# brick_3pin_led_1x1.net
KiCad netlist of a schematic drawn in EAGLE
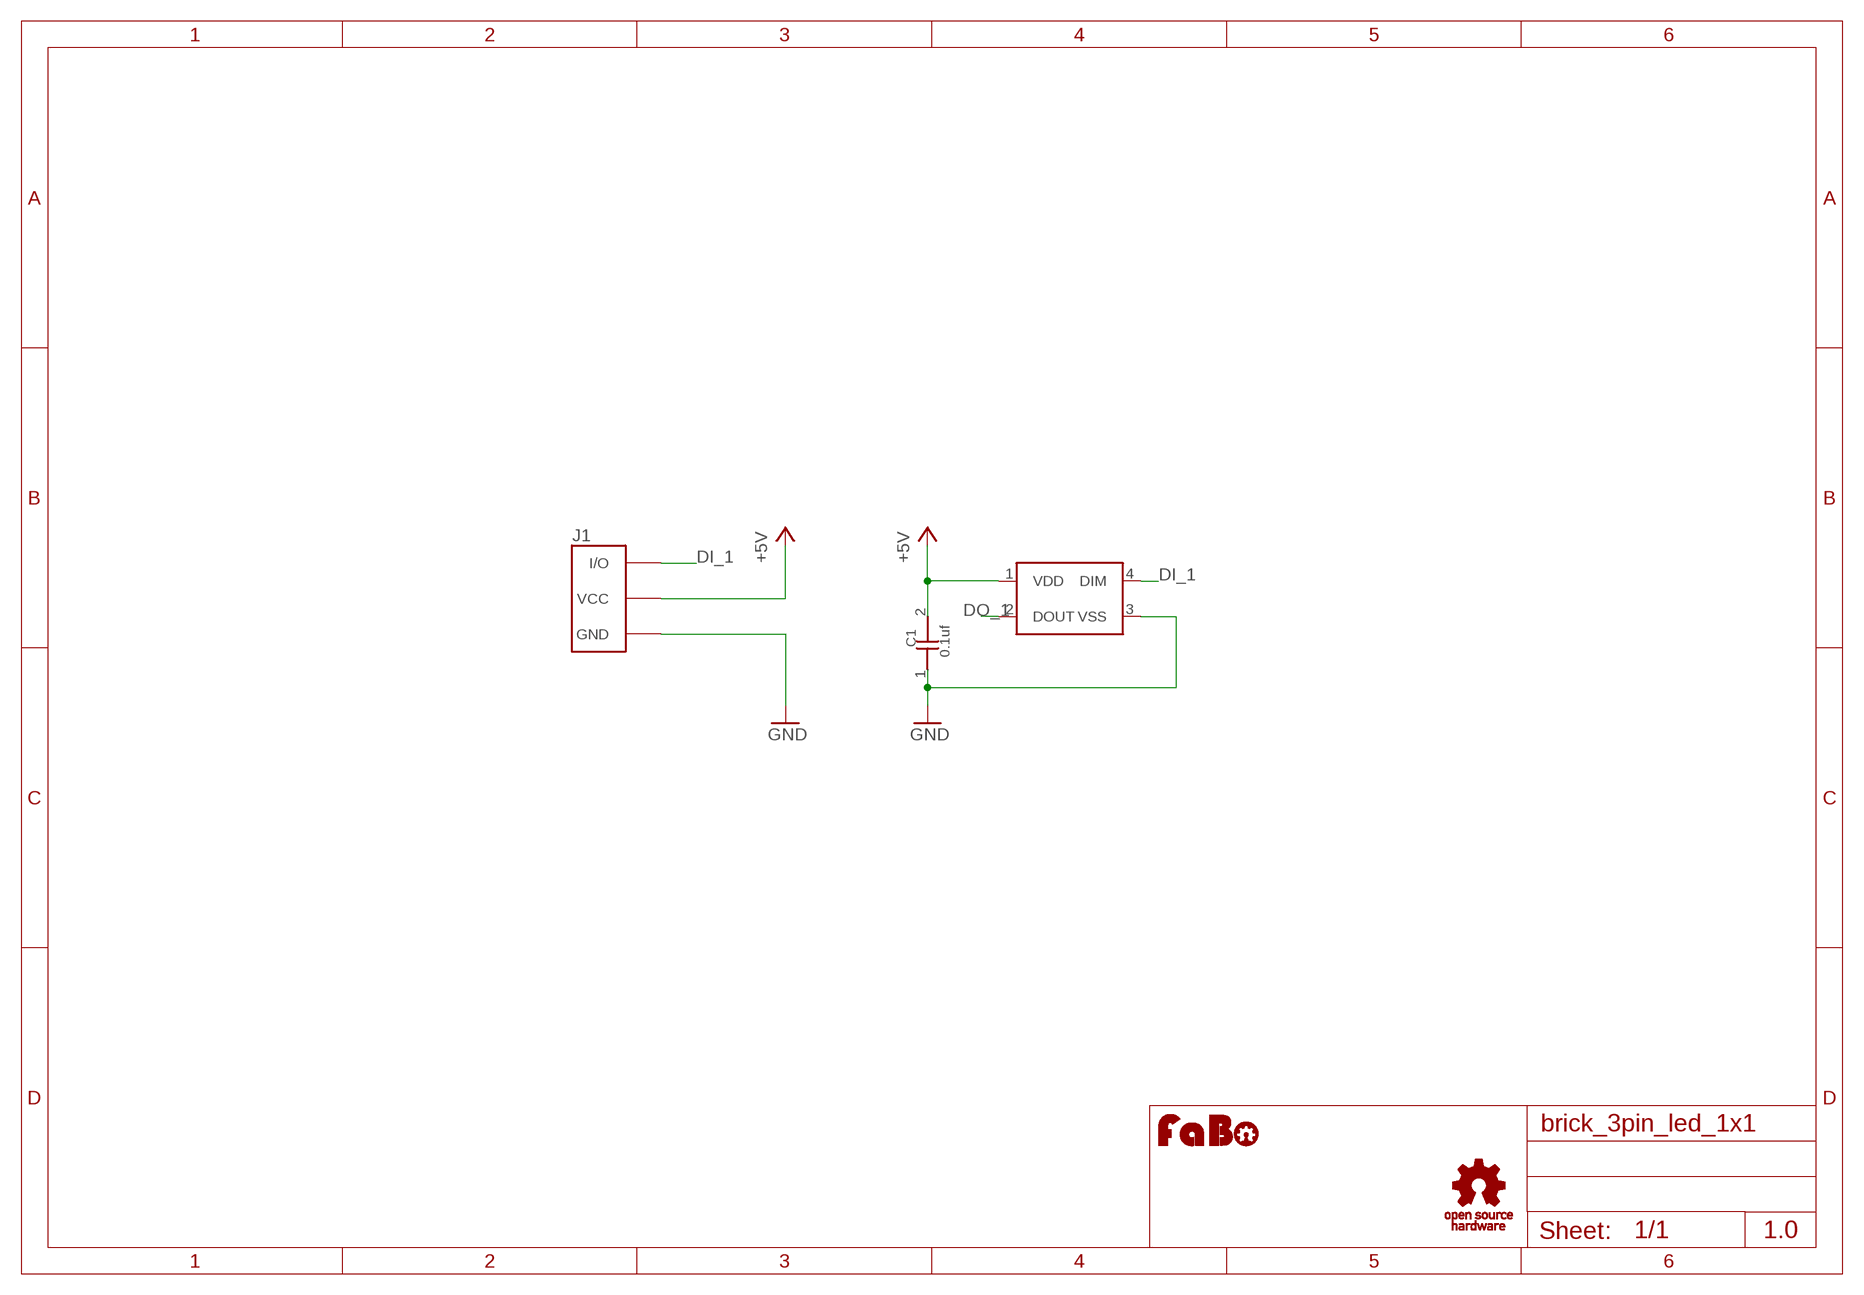
[diagram p0: schematic, sheet 1]

(export (version "E")
  (design (tool "Eeschema 10.0.6"))
  (components
    (comp (ref "C1")
      (value "0.1uf")
      (footprint "eagle-import:0603")
      (libsource (lib "eagle-import") (part "CAPACITOR0603"))
    )
    (comp (ref "J1")
      (value "BRICK_3PIN_NORMAL")
      (footprint "eagle-import:BRICK_3PIN")
      (libsource (lib "eagle-import") (part "BRICK_3PIN_NORMAL"))
    )
    (comp (ref "LED1")
      (value "WS2818B")
      (footprint "eagle-import:WS2818B")
      (libsource (lib "eagle-import") (part "WS2818B"))
    )
    (comp (ref "U$4")
      (value "LOGO_FABO-M")
      (footprint "eagle-import:LOGO_FABO_M")
      (libsource (lib "eagle-import") (part "LOGO_FABO-M"))
    )
    (comp (ref "U$5")
      (value "LOGO_OSHW_T-M")
      (footprint "eagle-import:LOGO_OSHW_T_M")
      (libsource (lib "eagle-import") (part "LOGO_OSHW_T-M"))
    )
  )
  (nets
    (net (code "1") (name "+5V") (class "Default")
      (node (ref "C1") (pin "2") (pinfunction "2_2") (pintype "passive"))
      (node (ref "J1") (pin "VCC") (pinfunction "VCC_VCC") (pintype "bidirectional"))
      (node (ref "LED1") (pin "1") (pinfunction "VDD_1") (pintype "bidirectional"))
    )
    (net (code "2") (name "/DI_1") (class "Default")
      (node (ref "J1") (pin "IN/OUT") (pinfunction "I/O_IN/OUT") (pintype "bidirectional"))
      (node (ref "LED1") (pin "4") (pinfunction "DIM_4") (pintype "bidirectional"))
    )
    (net (code "3") (name "/DO_1") (class "Default")
      (node (ref "LED1") (pin "2") (pinfunction "DOUT_2") (pintype "bidirectional"))
    )
    (net (code "4") (name "GND") (class "Default")
      (node (ref "C1") (pin "1") (pinfunction "1_1") (pintype "passive"))
      (node (ref "J1") (pin "GND") (pinfunction "GND_GND") (pintype "bidirectional"))
      (node (ref "LED1") (pin "3") (pinfunction "VSS_3") (pintype "bidirectional"))
    )
  )
)
